# CERVEAU_01b.net
KiCad netlist of a schematic drawn in EAGLE
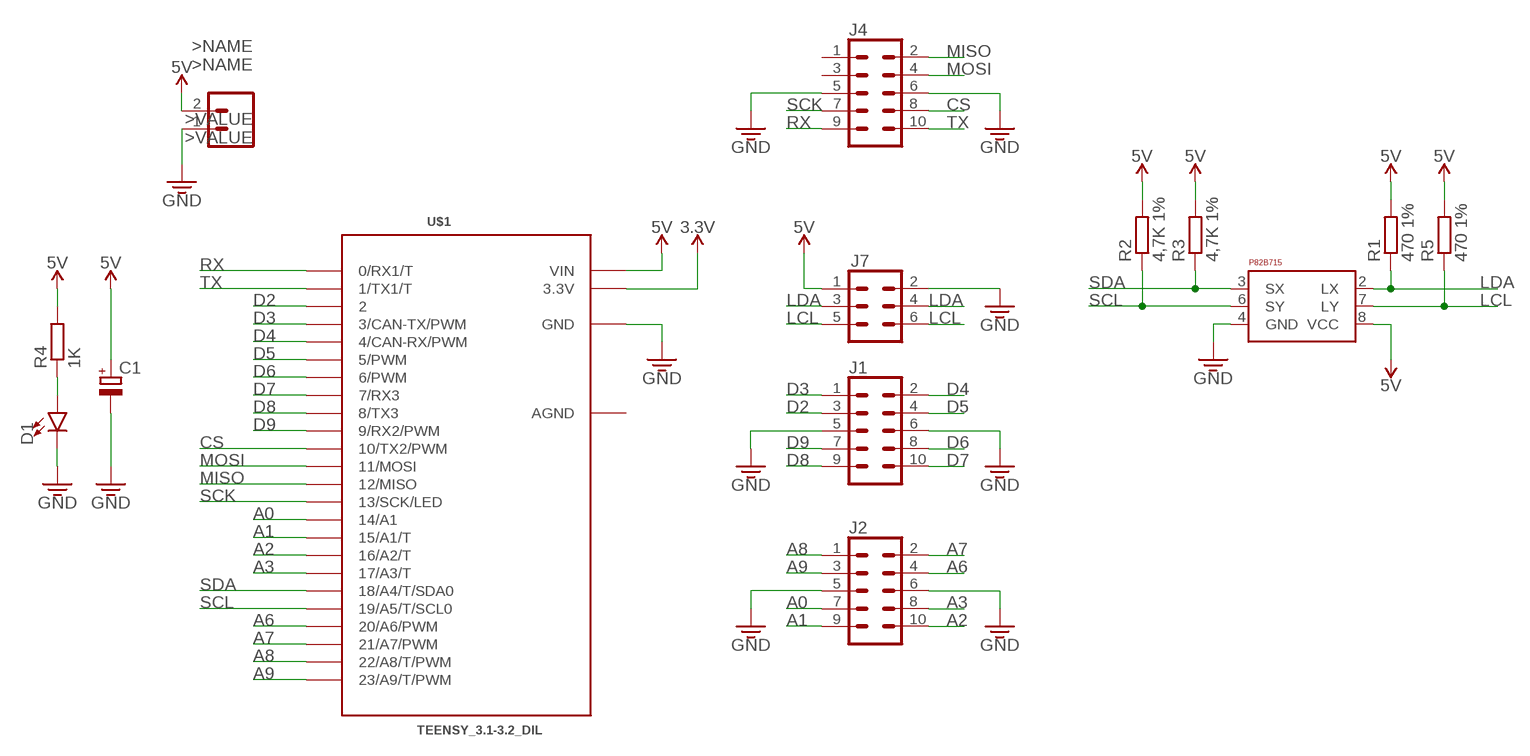
[diagram p0: schematic, sheet 1]

(export (version "E")
  (design (tool "Eeschema 10.0.6"))
  (components
    (comp (ref "C1")
      (value "CPOL-EUE2.5-6")
      (footprint "eagle-import:E2,5-6")
      (libsource (lib "eagle-import") (part "CPOL-EUE2.5-6"))
    )
    (comp (ref "D1")
      (value "LED5MM")
      (footprint "eagle-import:LED_5MM")
      (libsource (lib "eagle-import") (part "LED5MM"))
    )
    (comp (ref "J1")
      (value "CONN_05X2SHD")
      (footprint "eagle-import:2X5-SHROUDED")
      (libsource (lib "eagle-import") (part "CONN_05X2SHD"))
    )
    (comp (ref "J2")
      (value "CONN_05X2SHD")
      (footprint "eagle-import:2X5-SHROUDED")
      (libsource (lib "eagle-import") (part "CONN_05X2SHD"))
    )
    (comp (ref "J3")
      (value "CONN_02POLAR")
      (footprint "eagle-import:MOLEX-1X2")
      (libsource (lib "eagle-import") (part "CONN_02POLAR"))
    )
    (comp (ref "J4")
      (value "CONN_05X2SHD")
      (footprint "eagle-import:2X5-SHROUDED")
      (libsource (lib "eagle-import") (part "CONN_05X2SHD"))
    )
    (comp (ref "J7")
      (value "CONN_03X2SHROUD")
      (footprint "eagle-import:2X3-SHROUDED")
      (libsource (lib "eagle-import") (part "CONN_03X2SHROUD"))
    )
    (comp (ref "R1")
      (value "470 1%")
      (footprint "eagle-import:0207_2V")
      (libsource (lib "eagle-import") (part "R-EU_0207/2V"))
    )
    (comp (ref "R2")
      (value "4,7K 1%")
      (footprint "eagle-import:0207_2V")
      (libsource (lib "eagle-import") (part "R-EU_0207/2V"))
    )
    (comp (ref "R3")
      (value "4,7K 1%")
      (footprint "eagle-import:0207_2V")
      (libsource (lib "eagle-import") (part "R-EU_0207/2V"))
    )
    (comp (ref "R4")
      (value "1K")
      (footprint "eagle-import:0207_2V")
      (libsource (lib "eagle-import") (part "R-EU_0207/2V"))
    )
    (comp (ref "R5")
      (value "470 1%")
      (footprint "eagle-import:0207_2V")
      (libsource (lib "eagle-import") (part "R-EU_0207/2V"))
    )
    (comp (ref "U$1")
      (value "TEENSY_3.1-3.2_DIL")
      (footprint "eagle-import:TEENSY_3.0-3.2&LC_DIL")
      (libsource (lib "eagle-import") (part "TEENSY_3.1-3.2_DIL"))
    )
    (comp (ref "U$2")
      (value "P82B715")
      (footprint "eagle-import:SOCKET-08")
      (libsource (lib "eagle-import") (part "P82B715"))
    )
  )
  (nets
    (net (code "1") (name "/A0") (class "Default")
      (node (ref "J2") (pin "7") (pinfunction "7_7") (pintype "passive"))
      (node (ref "U$1") (pin "14/A0") (pinfunction "14/A1_14/A0") (pintype "bidirectional"))
    )
    (net (code "2") (name "/A1") (class "Default")
      (node (ref "J2") (pin "9") (pinfunction "9_9") (pintype "passive"))
      (node (ref "U$1") (pin "15/A1") (pinfunction "15/A1/T_15/A1") (pintype "bidirectional"))
    )
    (net (code "3") (name "/A2") (class "Default")
      (node (ref "J2") (pin "10") (pinfunction "10_10") (pintype "passive"))
      (node (ref "U$1") (pin "16/A2") (pinfunction "16/A2/T_16/A2") (pintype "bidirectional"))
    )
    (net (code "4") (name "/A3") (class "Default")
      (node (ref "J2") (pin "8") (pinfunction "8_8") (pintype "passive"))
      (node (ref "U$1") (pin "17/A3") (pinfunction "17/A3/T_17/A3") (pintype "bidirectional"))
    )
    (net (code "5") (name "/A6") (class "Default")
      (node (ref "J2") (pin "4") (pinfunction "4_4") (pintype "passive"))
      (node (ref "U$1") (pin "20/A6") (pinfunction "20/A6/PWM_20/A6") (pintype "bidirectional"))
    )
    (net (code "6") (name "/A7") (class "Default")
      (node (ref "J2") (pin "2") (pinfunction "2_2") (pintype "passive"))
      (node (ref "U$1") (pin "21/A7") (pinfunction "21/A7/PWM_21/A7") (pintype "bidirectional"))
    )
    (net (code "7") (name "/A8") (class "Default")
      (node (ref "J2") (pin "1") (pinfunction "1_1") (pintype "passive"))
      (node (ref "U$1") (pin "22/A8") (pinfunction "22/A8/T/PWM_22/A8") (pintype "bidirectional"))
    )
    (net (code "8") (name "/A9") (class "Default")
      (node (ref "J2") (pin "3") (pinfunction "3_3") (pintype "passive"))
      (node (ref "U$1") (pin "23/A9") (pinfunction "23/A9/T/PWM_23/A9") (pintype "bidirectional"))
    )
    (net (code "9") (name "/AGND") (class "Default")
      (node (ref "U$1") (pin "AGND") (pinfunction "AGND_AGND") (pintype "power_in"))
    )
    (net (code "10") (name "/CS") (class "Default")
      (node (ref "J4") (pin "8") (pinfunction "8_8") (pintype "passive"))
      (node (ref "U$1") (pin "10") (pinfunction "10/TX2/PWM_10") (pintype "bidirectional"))
    )
    (net (code "11") (name "/D2") (class "Default")
      (node (ref "J1") (pin "3") (pinfunction "3_3") (pintype "passive"))
      (node (ref "U$1") (pin "2") (pinfunction "2_2") (pintype "bidirectional"))
    )
    (net (code "12") (name "/D3") (class "Default")
      (node (ref "J1") (pin "1") (pinfunction "1_1") (pintype "passive"))
      (node (ref "U$1") (pin "3") (pinfunction "3/CAN-TX/PWM_3") (pintype "bidirectional"))
    )
    (net (code "13") (name "/D4") (class "Default")
      (node (ref "J1") (pin "2") (pinfunction "2_2") (pintype "passive"))
      (node (ref "U$1") (pin "4") (pinfunction "4/CAN-RX/PWM_4") (pintype "bidirectional"))
    )
    (net (code "14") (name "/D5") (class "Default")
      (node (ref "J1") (pin "4") (pinfunction "4_4") (pintype "passive"))
      (node (ref "U$1") (pin "5") (pinfunction "5/PWM_5") (pintype "bidirectional"))
    )
    (net (code "15") (name "/D6") (class "Default")
      (node (ref "J1") (pin "8") (pinfunction "8_8") (pintype "passive"))
      (node (ref "U$1") (pin "6") (pinfunction "6/PWM_6") (pintype "bidirectional"))
    )
    (net (code "16") (name "/D7") (class "Default")
      (node (ref "J1") (pin "10") (pinfunction "10_10") (pintype "passive"))
      (node (ref "U$1") (pin "7") (pinfunction "7/RX3_7") (pintype "bidirectional"))
    )
    (net (code "17") (name "/D8") (class "Default")
      (node (ref "J1") (pin "9") (pinfunction "9_9") (pintype "passive"))
      (node (ref "U$1") (pin "8") (pinfunction "8/TX3_8") (pintype "bidirectional"))
    )
    (net (code "18") (name "/D9") (class "Default")
      (node (ref "J1") (pin "7") (pinfunction "7_7") (pintype "passive"))
      (node (ref "U$1") (pin "9") (pinfunction "9/RX2/PWM_9") (pintype "bidirectional"))
    )
    (net (code "19") (name "/LCL") (class "Default")
      (node (ref "J7") (pin "5") (pinfunction "5_5") (pintype "bidirectional"))
      (node (ref "J7") (pin "6") (pinfunction "6_6") (pintype "bidirectional"))
      (node (ref "R5") (pin "1") (pinfunction "1_1") (pintype "passive"))
      (node (ref "U$2") (pin "7") (pinfunction "LY_7") (pintype "bidirectional"))
    )
    (net (code "20") (name "/LDA") (class "Default")
      (node (ref "J7") (pin "3") (pinfunction "3_3") (pintype "bidirectional"))
      (node (ref "J7") (pin "4") (pinfunction "4_4") (pintype "bidirectional"))
      (node (ref "R1") (pin "1") (pinfunction "1_1") (pintype "passive"))
      (node (ref "U$2") (pin "2") (pinfunction "LX_2") (pintype "bidirectional"))
    )
    (net (code "21") (name "/MISO") (class "Default")
      (node (ref "J4") (pin "2") (pinfunction "2_2") (pintype "passive"))
      (node (ref "U$1") (pin "12") (pinfunction "12/MISO_12") (pintype "bidirectional"))
    )
    (net (code "22") (name "/MOSI") (class "Default")
      (node (ref "J4") (pin "4") (pinfunction "4_4") (pintype "passive"))
      (node (ref "U$1") (pin "11") (pinfunction "11/MOSI_11") (pintype "bidirectional"))
    )
    (net (code "23") (name "/RX") (class "Default")
      (node (ref "J4") (pin "9") (pinfunction "9_9") (pintype "passive"))
      (node (ref "U$1") (pin "0") (pinfunction "0/RX1/T_0") (pintype "bidirectional"))
    )
    (net (code "24") (name "/SCK") (class "Default")
      (node (ref "J4") (pin "7") (pinfunction "7_7") (pintype "passive"))
      (node (ref "U$1") (pin "13") (pinfunction "13/SCK/LED_13") (pintype "bidirectional"))
    )
    (net (code "25") (name "/SCL") (class "Default")
      (node (ref "R2") (pin "1") (pinfunction "1_1") (pintype "passive"))
      (node (ref "U$1") (pin "19/A5") (pinfunction "19/A5/T/SCL0_19/A5") (pintype "bidirectional"))
      (node (ref "U$2") (pin "6") (pinfunction "SY_6") (pintype "bidirectional"))
    )
    (net (code "26") (name "/SDA") (class "Default")
      (node (ref "R3") (pin "1") (pinfunction "1_1") (pintype "passive"))
      (node (ref "U$1") (pin "18/A4") (pinfunction "18/A4/T/SDA0_18/A4") (pintype "bidirectional"))
      (node (ref "U$2") (pin "3") (pinfunction "SX_3") (pintype "bidirectional"))
    )
    (net (code "27") (name "/TX") (class "Default")
      (node (ref "J4") (pin "10") (pinfunction "10_10") (pintype "passive"))
      (node (ref "U$1") (pin "1") (pinfunction "1/TX1/T_1") (pintype "bidirectional"))
    )
    (net (code "28") (name "3.3V") (class "Default")
      (node (ref "U$1") (pin "3.3V") (pinfunction "3.3V_3.3V") (pintype "power_in"))
    )
    (net (code "29") (name "5V") (class "Default")
      (node (ref "C1") (pin "+") (pinfunction "+_+") (pintype "passive"))
      (node (ref "J3") (pin "2") (pinfunction "2_2") (pintype "passive"))
      (node (ref "J7") (pin "1") (pinfunction "1_1") (pintype "bidirectional"))
      (node (ref "R1") (pin "2") (pinfunction "2_2") (pintype "passive"))
      (node (ref "R2") (pin "2") (pinfunction "2_2") (pintype "passive"))
      (node (ref "R3") (pin "2") (pinfunction "2_2") (pintype "passive"))
      (node (ref "R4") (pin "2") (pinfunction "2_2") (pintype "passive"))
      (node (ref "R5") (pin "2") (pinfunction "2_2") (pintype "passive"))
      (node (ref "U$1") (pin "VIN") (pinfunction "VIN_VIN") (pintype "power_in"))
      (node (ref "U$2") (pin "8") (pinfunction "VCC_8") (pintype "bidirectional"))
    )
    (net (code "30") (name "GND") (class "Default")
      (node (ref "C1") (pin "-") (pinfunction "-_-") (pintype "passive"))
      (node (ref "D1") (pin "K") (pinfunction "C_K") (pintype "passive"))
      (node (ref "J1") (pin "5") (pinfunction "5_5") (pintype "passive"))
      (node (ref "J1") (pin "6") (pinfunction "6_6") (pintype "passive"))
      (node (ref "J2") (pin "5") (pinfunction "5_5") (pintype "passive"))
      (node (ref "J2") (pin "6") (pinfunction "6_6") (pintype "passive"))
      (node (ref "J3") (pin "1") (pinfunction "1_1") (pintype "passive"))
      (node (ref "J4") (pin "5") (pinfunction "5_5") (pintype "passive"))
      (node (ref "J4") (pin "6") (pinfunction "6_6") (pintype "passive"))
      (node (ref "J7") (pin "2") (pinfunction "2_2") (pintype "bidirectional"))
      (node (ref "U$1") (pin "GND") (pinfunction "GND_GND") (pintype "power_in"))
      (node (ref "U$2") (pin "4") (pinfunction "GND_4") (pintype "bidirectional"))
    )
    (net (code "31") (name "Net-(D1-PadA)") (class "Default")
      (node (ref "D1") (pin "A") (pinfunction "A_A") (pintype "passive"))
      (node (ref "R4") (pin "1") (pinfunction "1_1") (pintype "passive"))
    )
    (net (code "32") (name "unconnected-(J4-Pad1)") (class "Default")
      (node (ref "J4") (pin "1") (pinfunction "1_1") (pintype "passive"))
    )
    (net (code "33") (name "unconnected-(J4-Pad3)") (class "Default")
      (node (ref "J4") (pin "3") (pinfunction "3_3") (pintype "passive"))
    )
  )
)
